# WalkMod_B0.net
KiCad netlist of a schematic drawn in Altium Designer
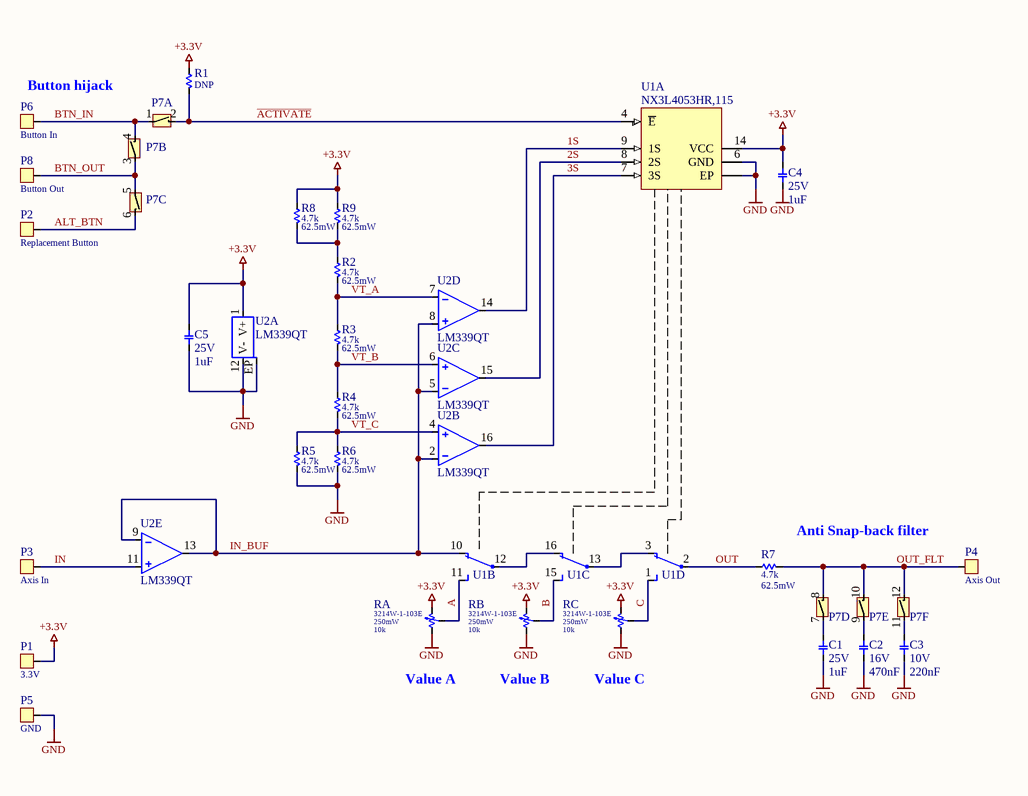
[diagram p0: WalkMod B0.SchDoc]

(export (version "E")
  (design (tool "Eeschema 10.0.6"))
  (components
    (comp (ref "C1")
      (value "1uF")
      (footprint "CX7R0603K")
      (description "1 µF ±10% 25V Ceramic Capacitor X7R 0603 (1608 Metric)")
      (fields (field (name "VALUE2") "25V") (field (name "Comment") "CL10B105KA8NFNC"))
      (libsource (lib "WalkMod") (part "kyocera-C-X7R-0603"))
    )
    (comp (ref "C2")
      (value "470nF")
      (footprint "CX7R0603K")
      (description "0.47 µF ±10% 16V Ceramic Capacitor X7R 0603 (1608 Metric)")
      (fields (field (name "VALUE2") "16V") (field (name "Comment") "CL10B474KO8NFNC"))
      (libsource (lib "WalkMod") (part "kyocera-C-X7R-0603"))
    )
    (comp (ref "C3")
      (value "220nF")
      (footprint "CX7R0603K")
      (description "0.22 µF ±10% 10V Ceramic Capacitor X7R 0603 (1608 Metric)")
      (fields (field (name "VALUE2") "10V") (field (name "Comment") "CC0603KRX7R6BB224"))
      (libsource (lib "WalkMod") (part "kyocera-C-X7R-0603"))
    )
    (comp (ref "C4")
      (value "1uF")
      (footprint "CX7R0603K")
      (description "1 µF ±10% 25V Ceramic Capacitor X7R 0603 (1608 Metric)")
      (fields (field (name "VALUE2") "25V") (field (name "Comment") "CL10B105KA8NFNC"))
      (libsource (lib "WalkMod") (part "kyocera-C-X7R-0603"))
    )
    (comp (ref "C5")
      (value "1uF")
      (footprint "CX7R0603K")
      (description "1 µF ±10% 25V Ceramic Capacitor X7R 0603 (1608 Metric)")
      (fields (field (name "VALUE2") "25V") (field (name "Comment") "CL10B105KA8NFNC"))
      (libsource (lib "WalkMod") (part "kyocera-C-X7R-0603"))
    )
    (comp (ref "P1")
      (value "SMD Pad 1 pin")
      (footprint "PAD_2X1.5_SQUARE")
      (description "Single SMD Pad")
      (fields (field (name "NAME") "3.3V"))
      (libsource (lib "WalkMod") (part "SMD Pad 1 pin"))
    )
    (comp (ref "P2")
      (value "SMD Pad 1 pin")
      (footprint "PAD_2X1.5_SQUARE")
      (description "Single SMD Pad")
      (fields (field (name "NAME") "Replacement Button"))
      (libsource (lib "WalkMod") (part "SMD Pad 1 pin"))
    )
    (comp (ref "P3")
      (value "SMD Pad 1 pin")
      (footprint "PAD_2X1.5_SQUARE")
      (description "Single SMD Pad")
      (fields (field (name "NAME") "Axis In"))
      (libsource (lib "WalkMod") (part "SMD Pad 1 pin"))
    )
    (comp (ref "P4")
      (value "SMD Pad 1 pin")
      (footprint "PAD_2X1.5_SQUARE")
      (description "Single SMD Pad")
      (fields (field (name "NAME") "Axis Out"))
      (libsource (lib "") (part "SMD Pad 1 pin_1"))
    )
    (comp (ref "P5")
      (value "SMD Pad 1 pin")
      (footprint "PAD_2X1.5_SQUARE")
      (description "Single SMD Pad")
      (fields (field (name "NAME") "GND"))
      (libsource (lib "WalkMod") (part "SMD Pad 1 pin"))
    )
    (comp (ref "P6")
      (value "SMD Pad 1 pin")
      (footprint "PAD_2X1.5_SQUARE")
      (description "Single SMD Pad")
      (fields (field (name "NAME") "Button In"))
      (libsource (lib "WalkMod") (part "SMD Pad 1 pin"))
    )
    (comp (ref "P7")
      (value "DS05-127-2-06BK-SMT-TR")
      (footprint "CUI-DS05-127-2-06BK-SMT_C")
      (description "Dip Switch SPST 6 Position Surface Mount Slide (Standard) Actuator 25mA 24VDC")
      (libsource (lib "WalkMod") (part "DS05-127-2-06BK-SMT-TR"))
    )
    (comp (ref "P8")
      (value "SMD Pad 1 pin")
      (footprint "PAD_2X1.5_SQUARE")
      (description "Single SMD Pad")
      (fields (field (name "NAME") "Button Out"))
      (libsource (lib "WalkMod") (part "SMD Pad 1 pin"))
    )
    (comp (ref "R1")
      (value "DNP")
      (footprint "AT0402_C")
      (libsource (lib "WalkMod") (part "AT0402FRE0710KL"))
    )
    (comp (ref "R2")
      (value "4.7k")
      (footprint "RT0402_C")
      (fields (field (name "VALUE2") "62.5mW") (field (name "Comment") "RG1005P-472-B-T5"))
      (libsource (lib "WalkMod") (part "RT0402DRD0747KL"))
    )
    (comp (ref "R3")
      (value "4.7k")
      (footprint "RT0402_C")
      (fields (field (name "VALUE2") "62.5mW") (field (name "Comment") "RG1005P-472-B-T5"))
      (libsource (lib "WalkMod") (part "RT0402DRD0747KL"))
    )
    (comp (ref "R4")
      (value "4.7k")
      (footprint "RT0402_C")
      (fields (field (name "VALUE2") "62.5mW") (field (name "Comment") "RG1005P-472-B-T5"))
      (libsource (lib "WalkMod") (part "RT0402DRD0747KL"))
    )
    (comp (ref "R5")
      (value "4.7k")
      (footprint "RT0402_C")
      (fields (field (name "VALUE2") "62.5mW") (field (name "Comment") "RG1005P-472-B-T5"))
      (libsource (lib "WalkMod") (part "RT0402DRD0747KL"))
    )
    (comp (ref "R6")
      (value "4.7k")
      (footprint "RT0402_C")
      (fields (field (name "VALUE2") "62.5mW") (field (name "Comment") "RG1005P-472-B-T5"))
      (libsource (lib "WalkMod") (part "RT0402DRD0747KL"))
    )
    (comp (ref "R7")
      (value "4.7k")
      (footprint "RT0402_C")
      (fields (field (name "VALUE2") "62.5mW") (field (name "Comment") "RG1005P-472-B-T5"))
      (libsource (lib "WalkMod") (part "RT0402DRD0747KL"))
    )
    (comp (ref "R8")
      (value "4.7k")
      (footprint "RT0402_C")
      (fields (field (name "VALUE2") "62.5mW") (field (name "Comment") "RG1005P-472-B-T5"))
      (libsource (lib "WalkMod") (part "RT0402DRD0747KL"))
    )
    (comp (ref "R9")
      (value "4.7k")
      (footprint "RT0402_C")
      (fields (field (name "VALUE2") "62.5mW") (field (name "Comment") "RG1005P-472-B-T5"))
      (libsource (lib "WalkMod") (part "RT0402DRD0747KL"))
    )
    (comp (ref "RA")
      (value "3214W-1-103E")
      (footprint "BOURNS_3214W_C")
      (description "10 kOhms 0.25W, 1/4W J Lead Surface Mount Trimmer Potentiometer Cermet 5.0 Turn Top Adjustment")
      (fields (field (name "VALUE2") "250mW") (field (name "ALTIUM_VALUE") "10k"))
      (libsource (lib "WalkMod") (part "3214W-1-103E"))
    )
    (comp (ref "RB")
      (value "3214W-1-103E")
      (footprint "BOURNS_3214W_C")
      (description "10 kOhms 0.25W, 1/4W J Lead Surface Mount Trimmer Potentiometer Cermet 5.0 Turn Top Adjustment")
      (fields (field (name "VALUE2") "250mW") (field (name "ALTIUM_VALUE") "10k"))
      (libsource (lib "WalkMod") (part "3214W-1-103E"))
    )
    (comp (ref "RC")
      (value "3214W-1-103E")
      (footprint "BOURNS_3214W_C")
      (description "10 kOhms 0.25W, 1/4W J Lead Surface Mount Trimmer Potentiometer Cermet 5.0 Turn Top Adjustment")
      (fields (field (name "VALUE2") "250mW") (field (name "ALTIUM_VALUE") "10k"))
      (libsource (lib "WalkMod") (part "3214W-1-103E"))
    )
    (comp (ref "U1")
      (value "NX3L4053HR,115")
      (footprint "HXQFN16_SOT1039-2_C")
      (description "3 Circuit IC Switch 2:1 800mOhm 16-HXQFN (3x3)")
      (libsource (lib "") (part "NX3L4053_1"))
    )
    (comp (ref "U2")
      (value "LM339QT")
      (footprint "QFN16_0.5_C")
      (description "Comparator General Purpose CMOS, DTL, ECL, MOS, Open-Collector, TTL 16-QFN (3x3)")
      (libsource (lib "") (part "LM339QT_1"))
    )
  )
  (nets
    (net (code "1") (name "+3.3V") (class "Default")
      (node (ref "C4") (pin "2") (pinfunction "2_2") (pintype "passive"))
      (node (ref "C5") (pin "2") (pinfunction "2_2") (pintype "passive"))
      (node (ref "P1") (pin "1") (pinfunction "1_1") (pintype "passive"))
      (node (ref "R1") (pin "1") (pinfunction "1_1") (pintype "passive"))
      (node (ref "R8") (pin "2") (pinfunction "2_2") (pintype "passive"))
      (node (ref "R9") (pin "2") (pinfunction "2_2") (pintype "passive"))
      (node (ref "RA") (pin "3") (pinfunction "3_3") (pintype "passive"))
      (node (ref "RB") (pin "3") (pinfunction "3_3") (pintype "passive"))
      (node (ref "RC") (pin "3") (pinfunction "3_3") (pintype "passive"))
      (node (ref "U1") (pin "14") (pinfunction "VCC_14") (pintype "power_in"))
      (node (ref "U2") (pin "1") (pinfunction "V+_1") (pintype "passive"))
    )
    (net (code "2") (name "/1S") (class "Default")
      (node (ref "U1") (pin "9") (pinfunction "1S_9") (pintype "input"))
      (node (ref "U2") (pin "14") (pinfunction "OUT3_14") (pintype "passive"))
    )
    (net (code "3") (name "/2S") (class "Default")
      (node (ref "U1") (pin "8") (pinfunction "2S_8") (pintype "input"))
      (node (ref "U2") (pin "15") (pinfunction "OUT2_15") (pintype "passive"))
    )
    (net (code "4") (name "/3S") (class "Default")
      (node (ref "U1") (pin "7") (pinfunction "3S_7") (pintype "input"))
      (node (ref "U2") (pin "16") (pinfunction "OUT1_16") (pintype "passive"))
    )
    (net (code "5") (name "/A") (class "Default")
      (node (ref "RA") (pin "2") (pinfunction "2_2") (pintype "passive"))
      (node (ref "U1") (pin "11") (pinfunction "1Y1_11") (pintype "passive"))
    )
    (net (code "6") (name "/ALT_BTN") (class "Default")
      (node (ref "P2") (pin "1") (pinfunction "1_1") (pintype "passive"))
      (node (ref "P7") (pin "6") (pinfunction "6_6") (pintype "passive"))
    )
    (net (code "7") (name "/B") (class "Default")
      (node (ref "RB") (pin "2") (pinfunction "2_2") (pintype "passive"))
      (node (ref "U1") (pin "15") (pinfunction "2Y1_15") (pintype "passive"))
    )
    (net (code "8") (name "/BTN_IN") (class "Default")
      (node (ref "P6") (pin "1") (pinfunction "1_1") (pintype "passive"))
      (node (ref "P7") (pin "1") (pinfunction "1_1") (pintype "passive"))
      (node (ref "P7") (pin "4") (pinfunction "4_4") (pintype "passive"))
    )
    (net (code "9") (name "/BTN_OUT") (class "Default")
      (node (ref "P7") (pin "3") (pinfunction "3_3") (pintype "passive"))
      (node (ref "P7") (pin "5") (pinfunction "5_5") (pintype "passive"))
      (node (ref "P8") (pin "1") (pinfunction "1_1") (pintype "passive"))
    )
    (net (code "10") (name "/C") (class "Default")
      (node (ref "RC") (pin "2") (pinfunction "2_2") (pintype "passive"))
      (node (ref "U1") (pin "1") (pinfunction "3Y1_1") (pintype "passive"))
    )
    (net (code "11") (name "/IN") (class "Default")
      (node (ref "P3") (pin "1") (pinfunction "1_1") (pintype "passive"))
      (node (ref "U2") (pin "11") (pinfunction "IN+4_11") (pintype "passive"))
    )
    (net (code "12") (name "/IN_BUF") (class "Default")
      (node (ref "U1") (pin "10") (pinfunction "1Y0_10") (pintype "passive"))
      (node (ref "U2") (pin "13") (pinfunction "OUT4_13") (pintype "passive"))
      (node (ref "U2") (pin "2") (pinfunction "IN-1_2") (pintype "passive"))
      (node (ref "U2") (pin "5") (pinfunction "IN-2_5") (pintype "passive"))
      (node (ref "U2") (pin "8") (pinfunction "IN+3_8") (pintype "passive"))
      (node (ref "U2") (pin "9") (pinfunction "IN-4_9") (pintype "passive"))
    )
    (net (code "13") (name "/OUT") (class "Default")
      (node (ref "R7") (pin "2") (pinfunction "2_2") (pintype "passive"))
      (node (ref "U1") (pin "2") (pinfunction "3Z_2") (pintype "passive"))
    )
    (net (code "14") (name "/OUT_FLT") (class "Default")
      (node (ref "P4") (pin "1") (pinfunction "1_1") (pintype "passive"))
      (node (ref "P7") (pin "10") (pinfunction "10_10") (pintype "passive"))
      (node (ref "P7") (pin "12") (pinfunction "12_12") (pintype "passive"))
      (node (ref "P7") (pin "8") (pinfunction "8_8") (pintype "passive"))
      (node (ref "R7") (pin "1") (pinfunction "1_1") (pintype "passive"))
    )
    (net (code "15") (name "/VT_A") (class "Default")
      (node (ref "R2") (pin "1") (pinfunction "1_1") (pintype "passive"))
      (node (ref "R3") (pin "2") (pinfunction "2_2") (pintype "passive"))
      (node (ref "U2") (pin "7") (pinfunction "IN-3_7") (pintype "passive"))
    )
    (net (code "16") (name "/VT_B") (class "Default")
      (node (ref "R3") (pin "1") (pinfunction "1_1") (pintype "passive"))
      (node (ref "R4") (pin "2") (pinfunction "2_2") (pintype "passive"))
      (node (ref "U2") (pin "6") (pinfunction "IN+2_6") (pintype "passive"))
    )
    (net (code "17") (name "/VT_C") (class "Default")
      (node (ref "R4") (pin "1") (pinfunction "1_1") (pintype "passive"))
      (node (ref "R5") (pin "2") (pinfunction "2_2") (pintype "passive"))
      (node (ref "R6") (pin "2") (pinfunction "2_2") (pintype "passive"))
      (node (ref "U2") (pin "4") (pinfunction "IN+1_4") (pintype "passive"))
    )
    (net (code "18") (name "/~{ACTIVATE}") (class "Default")
      (node (ref "P7") (pin "2") (pinfunction "2_2") (pintype "passive"))
      (node (ref "R1") (pin "2") (pinfunction "2_2") (pintype "passive"))
      (node (ref "U1") (pin "4") (pinfunction "~{E}_4") (pintype "input"))
    )
    (net (code "19") (name "GND") (class "Default")
      (node (ref "C1") (pin "1") (pinfunction "1_1") (pintype "passive"))
      (node (ref "C2") (pin "1") (pinfunction "1_1") (pintype "passive"))
      (node (ref "C3") (pin "1") (pinfunction "1_1") (pintype "passive"))
      (node (ref "C4") (pin "1") (pinfunction "1_1") (pintype "passive"))
      (node (ref "C5") (pin "1") (pinfunction "1_1") (pintype "passive"))
      (node (ref "P5") (pin "1") (pinfunction "1_1") (pintype "passive"))
      (node (ref "R5") (pin "1") (pinfunction "1_1") (pintype "passive"))
      (node (ref "R6") (pin "1") (pinfunction "1_1") (pintype "passive"))
      (node (ref "RA") (pin "1") (pinfunction "1_1") (pintype "passive"))
      (node (ref "RB") (pin "1") (pinfunction "1_1") (pintype "passive"))
      (node (ref "RC") (pin "1") (pinfunction "1_1") (pintype "passive"))
      (node (ref "U1") (pin "6") (pinfunction "GND_6") (pintype "power_in"))
      (node (ref "U1") (pin "EP") (pinfunction "EP_EP") (pintype "power_in"))
      (node (ref "U2") (pin "12") (pinfunction "V-_12") (pintype "passive"))
      (node (ref "U2") (pin "EP") (pinfunction "EP_EP") (pintype "passive"))
    )
    (net (code "20") (name "Net-(C1-Pad2)") (class "Default")
      (node (ref "C1") (pin "2") (pinfunction "2_2") (pintype "passive"))
      (node (ref "P7") (pin "7") (pinfunction "7_7") (pintype "passive"))
    )
    (net (code "21") (name "Net-(C2-Pad2)") (class "Default")
      (node (ref "C2") (pin "2") (pinfunction "2_2") (pintype "passive"))
      (node (ref "P7") (pin "9") (pinfunction "9_9") (pintype "passive"))
    )
    (net (code "22") (name "Net-(C3-Pad2)") (class "Default")
      (node (ref "C3") (pin "2") (pinfunction "2_2") (pintype "passive"))
      (node (ref "P7") (pin "11") (pinfunction "11_11") (pintype "passive"))
    )
    (net (code "23") (name "Net-(R2-Pad2)") (class "Default")
      (node (ref "R2") (pin "2") (pinfunction "2_2") (pintype "passive"))
      (node (ref "R8") (pin "1") (pinfunction "1_1") (pintype "passive"))
      (node (ref "R9") (pin "1") (pinfunction "1_1") (pintype "passive"))
    )
    (net (code "24") (name "Net-(U1B-1Z)") (class "Default")
      (node (ref "U1") (pin "12") (pinfunction "1Z_12") (pintype "passive"))
      (node (ref "U1") (pin "16") (pinfunction "2Y0_16") (pintype "passive"))
    )
    (net (code "25") (name "Net-(U1C-2Z)") (class "Default")
      (node (ref "U1") (pin "13") (pinfunction "2Z_13") (pintype "passive"))
      (node (ref "U1") (pin "3") (pinfunction "3Y0_3") (pintype "passive"))
    )
  )
)
